# temp_presX3.net
KiCad netlist of a schematic drawn in Altium Designer
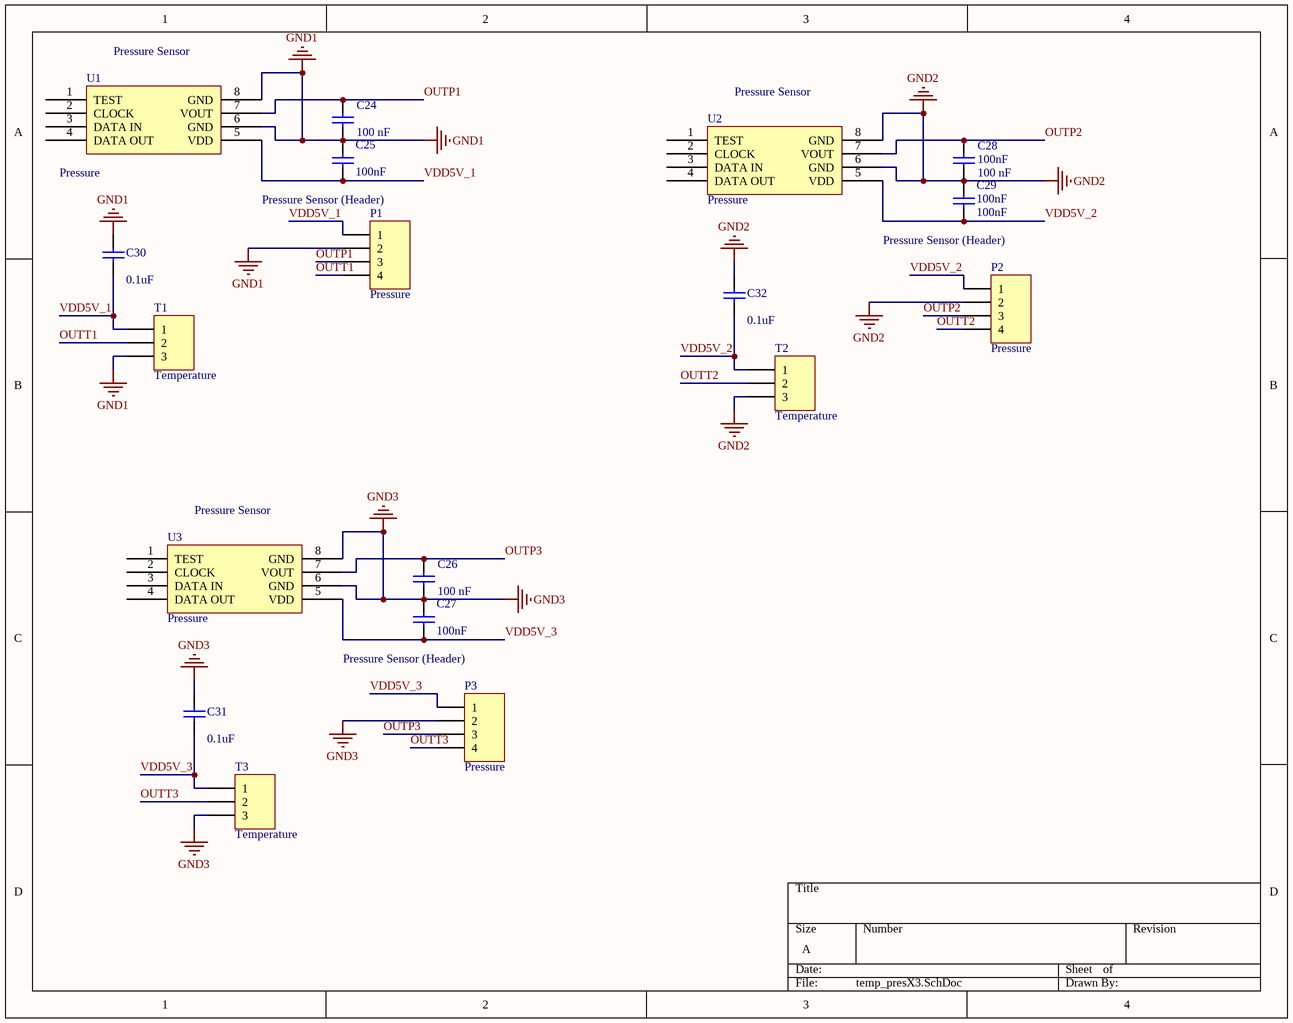
[diagram p0: temp_presX3.SchDoc]

(export (version "E")
  (design (tool "Eeschema 10.0.6"))
  (components
    (comp (ref "C24")
      (value "100 nF")
      (footprint "C1206")
      (description "Capacitor (Semiconductor SIM Model)")
      (fields (field (name "Comment") "100nF") (field (name "PUBLISHER") "Altium Limited"))
      (libsource (lib "Miscellaneous Devices") (part "Cap Semi"))
    )
    (comp (ref "C25")
      (value "100nF")
      (footprint "C1206")
      (description "Capacitor (Semiconductor SIM Model)")
      (fields (field (name "PUBLISHER") "Altium Limited"))
      (libsource (lib "Miscellaneous Devices") (part "Cap Semi"))
    )
    (comp (ref "C26")
      (value "100 nF")
      (footprint "C1206")
      (description "Capacitor (Semiconductor SIM Model)")
      (fields (field (name "Comment") "100nF") (field (name "PUBLISHER") "Altium Limited"))
      (libsource (lib "Miscellaneous Devices") (part "Cap Semi"))
    )
    (comp (ref "C27")
      (value "100nF")
      (footprint "C1206")
      (description "Capacitor (Semiconductor SIM Model)")
      (fields (field (name "PUBLISHER") "Altium Limited"))
      (libsource (lib "Miscellaneous Devices") (part "Cap Semi"))
    )
    (comp (ref "C28")
      (value "100nF")
      (footprint "C1206")
      (description "Capacitor (Semiconductor SIM Model)")
      (fields (field (name "ALTIUM_VALUE") "100 nF") (field (name "PUBLISHER") "Altium Limited"))
      (libsource (lib "Miscellaneous Devices") (part "Cap Semi"))
    )
    (comp (ref "C29")
      (value "100nF")
      (footprint "C1206")
      (description "Capacitor (Semiconductor SIM Model)")
      (fields (field (name "ALTIUM_VALUE") "100nF") (field (name "PUBLISHER") "Altium Limited"))
      (libsource (lib "Miscellaneous Devices") (part "Cap Semi"))
    )
    (comp (ref "C30")
      (value "0.1uF")
      (footprint "C1206")
      (description "Capacitor (Semiconductor SIM Model)")
      (fields (field (name "PUBLISHER") "Altium Limited"))
      (libsource (lib "Miscellaneous Devices") (part "Cap Semi"))
    )
    (comp (ref "C31")
      (value "0.1uF")
      (footprint "C1206")
      (description "Capacitor (Semiconductor SIM Model)")
      (fields (field (name "PUBLISHER") "Altium Limited"))
      (libsource (lib "Miscellaneous Devices") (part "Cap Semi"))
    )
    (comp (ref "C32")
      (value "0.1uF")
      (footprint "C1206")
      (description "Capacitor (Semiconductor SIM Model)")
      (fields (field (name "PUBLISHER") "Altium Limited"))
      (libsource (lib "Miscellaneous Devices") (part "Cap Semi"))
    )
    (comp (ref "P1")
      (value "Pressure")
      (footprint "HDR1X4")
      (description "Header, 4-Pin")
      (fields (field (name "PUBLISHER") "Altium Limited"))
      (libsource (lib "Miscellaneous Connectors") (part "Header 4"))
    )
    (comp (ref "P2")
      (value "Pressure")
      (footprint "HDR1X4")
      (description "Header, 4-Pin")
      (fields (field (name "PUBLISHER") "Altium Limited"))
      (libsource (lib "Miscellaneous Connectors") (part "Header 4"))
    )
    (comp (ref "P3")
      (value "Pressure")
      (footprint "HDR1X4")
      (description "Header, 4-Pin")
      (fields (field (name "PUBLISHER") "Altium Limited"))
      (libsource (lib "Miscellaneous Connectors") (part "Header 4"))
    )
    (comp (ref "T1")
      (value "Temperature")
      (footprint "HDR1X3")
      (description "Header, 3-Pin")
      (fields (field (name "PUBLISHER") "Altium Limited"))
      (libsource (lib "Miscellaneous Connectors") (part "Header 3"))
    )
    (comp (ref "T2")
      (value "Temperature")
      (footprint "HDR1X3")
      (description "Header, 3-Pin")
      (fields (field (name "PUBLISHER") "Altium Limited"))
      (libsource (lib "Miscellaneous Connectors") (part "Header 3"))
    )
    (comp (ref "T3")
      (value "Temperature")
      (footprint "HDR1X3")
      (description "Header, 3-Pin")
      (fields (field (name "PUBLISHER") "Altium Limited"))
      (libsource (lib "Miscellaneous Connectors") (part "Header 3"))
    )
    (comp (ref "U1") (value "Pressure") (footprint "KP-234") (libsource (lib "KP234") (part "Component_1")))
    (comp (ref "U2") (value "Pressure") (footprint "KP-234") (libsource (lib "KP234") (part "Component_1")))
    (comp (ref "U3") (value "Pressure") (footprint "KP-234") (libsource (lib "KP234") (part "Component_1")))
  )
  (nets
    (net (code "1") (name "/OUTP1") (class "Default")
      (node (ref "C24") (pin "2") (pinfunction "2_2") (pintype "passive"))
      (node (ref "P1") (pin "3") (pinfunction "3_3") (pintype "passive"))
      (node (ref "U1") (pin "7") (pinfunction "VOUT_7") (pintype "passive"))
    )
    (net (code "2") (name "/OUTP2") (class "Default")
      (node (ref "C28") (pin "2") (pinfunction "2_2") (pintype "passive"))
      (node (ref "P2") (pin "3") (pinfunction "3_3") (pintype "passive"))
      (node (ref "U2") (pin "7") (pinfunction "VOUT_7") (pintype "passive"))
    )
    (net (code "3") (name "/OUTP3") (class "Default")
      (node (ref "C26") (pin "2") (pinfunction "2_2") (pintype "passive"))
      (node (ref "P3") (pin "3") (pinfunction "3_3") (pintype "passive"))
      (node (ref "U3") (pin "7") (pinfunction "VOUT_7") (pintype "passive"))
    )
    (net (code "4") (name "/OUTT1") (class "Default")
      (node (ref "P1") (pin "4") (pinfunction "4_4") (pintype "passive"))
      (node (ref "T1") (pin "2") (pinfunction "2_2") (pintype "passive"))
    )
    (net (code "5") (name "/OUTT2") (class "Default")
      (node (ref "P2") (pin "4") (pinfunction "4_4") (pintype "passive"))
      (node (ref "T2") (pin "2") (pinfunction "2_2") (pintype "passive"))
    )
    (net (code "6") (name "/OUTT3") (class "Default")
      (node (ref "P3") (pin "4") (pinfunction "4_4") (pintype "passive"))
      (node (ref "T3") (pin "2") (pinfunction "2_2") (pintype "passive"))
    )
    (net (code "7") (name "/VDD5V_1") (class "Default")
      (node (ref "C25") (pin "1") (pinfunction "1_1") (pintype "passive"))
      (node (ref "C30") (pin "1") (pinfunction "1_1") (pintype "passive"))
      (node (ref "P1") (pin "1") (pinfunction "1_1") (pintype "passive"))
      (node (ref "T1") (pin "1") (pinfunction "1_1") (pintype "passive"))
      (node (ref "U1") (pin "5") (pinfunction "VDD_5") (pintype "passive"))
    )
    (net (code "8") (name "/VDD5V_2") (class "Default")
      (node (ref "C29") (pin "1") (pinfunction "1_1") (pintype "passive"))
      (node (ref "C32") (pin "1") (pinfunction "1_1") (pintype "passive"))
      (node (ref "P2") (pin "1") (pinfunction "1_1") (pintype "passive"))
      (node (ref "T2") (pin "1") (pinfunction "1_1") (pintype "passive"))
      (node (ref "U2") (pin "5") (pinfunction "VDD_5") (pintype "passive"))
    )
    (net (code "9") (name "/VDD5V_3") (class "Default")
      (node (ref "C27") (pin "1") (pinfunction "1_1") (pintype "passive"))
      (node (ref "C31") (pin "1") (pinfunction "1_1") (pintype "passive"))
      (node (ref "P3") (pin "1") (pinfunction "1_1") (pintype "passive"))
      (node (ref "T3") (pin "1") (pinfunction "1_1") (pintype "passive"))
      (node (ref "U3") (pin "5") (pinfunction "VDD_5") (pintype "passive"))
    )
    (net (code "10") (name "GND1") (class "Default")
      (node (ref "C24") (pin "1") (pinfunction "1_1") (pintype "passive"))
      (node (ref "C25") (pin "2") (pinfunction "2_2") (pintype "passive"))
      (node (ref "C30") (pin "2") (pinfunction "2_2") (pintype "passive"))
      (node (ref "P1") (pin "2") (pinfunction "2_2") (pintype "passive"))
      (node (ref "T1") (pin "3") (pinfunction "3_3") (pintype "passive"))
      (node (ref "U1") (pin "6") (pinfunction "GND_6") (pintype "passive"))
      (node (ref "U1") (pin "8") (pinfunction "GND_8") (pintype "passive"))
    )
    (net (code "11") (name "GND2") (class "Default")
      (node (ref "C28") (pin "1") (pinfunction "1_1") (pintype "passive"))
      (node (ref "C29") (pin "2") (pinfunction "2_2") (pintype "passive"))
      (node (ref "C32") (pin "2") (pinfunction "2_2") (pintype "passive"))
      (node (ref "P2") (pin "2") (pinfunction "2_2") (pintype "passive"))
      (node (ref "T2") (pin "3") (pinfunction "3_3") (pintype "passive"))
      (node (ref "U2") (pin "6") (pinfunction "GND_6") (pintype "passive"))
      (node (ref "U2") (pin "8") (pinfunction "GND_8") (pintype "passive"))
    )
    (net (code "12") (name "GND3") (class "Default")
      (node (ref "C26") (pin "1") (pinfunction "1_1") (pintype "passive"))
      (node (ref "C27") (pin "2") (pinfunction "2_2") (pintype "passive"))
      (node (ref "C31") (pin "2") (pinfunction "2_2") (pintype "passive"))
      (node (ref "P3") (pin "2") (pinfunction "2_2") (pintype "passive"))
      (node (ref "T3") (pin "3") (pinfunction "3_3") (pintype "passive"))
      (node (ref "U3") (pin "6") (pinfunction "GND_6") (pintype "passive"))
      (node (ref "U3") (pin "8") (pinfunction "GND_8") (pintype "passive"))
    )
    (net (code "13") (name "unconnected-(U1-CLOCK-Pad2)") (class "Default")
      (node (ref "U1") (pin "2") (pinfunction "CLOCK_2") (pintype "passive"))
    )
    (net (code "14") (name "unconnected-(U1-DATA_IN-Pad3)") (class "Default")
      (node (ref "U1") (pin "3") (pinfunction "DATA_IN_3") (pintype "passive"))
    )
    (net (code "15") (name "unconnected-(U1-DATA_OUT-Pad4)") (class "Default")
      (node (ref "U1") (pin "4") (pinfunction "DATA_OUT_4") (pintype "passive"))
    )
    (net (code "16") (name "unconnected-(U1-TEST-Pad1)") (class "Default")
      (node (ref "U1") (pin "1") (pinfunction "TEST_1") (pintype "passive"))
    )
    (net (code "17") (name "unconnected-(U2-CLOCK-Pad2)") (class "Default")
      (node (ref "U2") (pin "2") (pinfunction "CLOCK_2") (pintype "passive"))
    )
    (net (code "18") (name "unconnected-(U2-DATA_IN-Pad3)") (class "Default")
      (node (ref "U2") (pin "3") (pinfunction "DATA_IN_3") (pintype "passive"))
    )
    (net (code "19") (name "unconnected-(U2-DATA_OUT-Pad4)") (class "Default")
      (node (ref "U2") (pin "4") (pinfunction "DATA_OUT_4") (pintype "passive"))
    )
    (net (code "20") (name "unconnected-(U2-TEST-Pad1)") (class "Default")
      (node (ref "U2") (pin "1") (pinfunction "TEST_1") (pintype "passive"))
    )
    (net (code "21") (name "unconnected-(U3-CLOCK-Pad2)") (class "Default")
      (node (ref "U3") (pin "2") (pinfunction "CLOCK_2") (pintype "passive"))
    )
    (net (code "22") (name "unconnected-(U3-DATA_IN-Pad3)") (class "Default")
      (node (ref "U3") (pin "3") (pinfunction "DATA_IN_3") (pintype "passive"))
    )
    (net (code "23") (name "unconnected-(U3-DATA_OUT-Pad4)") (class "Default")
      (node (ref "U3") (pin "4") (pinfunction "DATA_OUT_4") (pintype "passive"))
    )
    (net (code "24") (name "unconnected-(U3-TEST-Pad1)") (class "Default")
      (node (ref "U3") (pin "1") (pinfunction "TEST_1") (pintype "passive"))
    )
  )
)
